# faketec-yuri_v1_1.net
KiCad netlist of a schematic drawn in Altium Designer
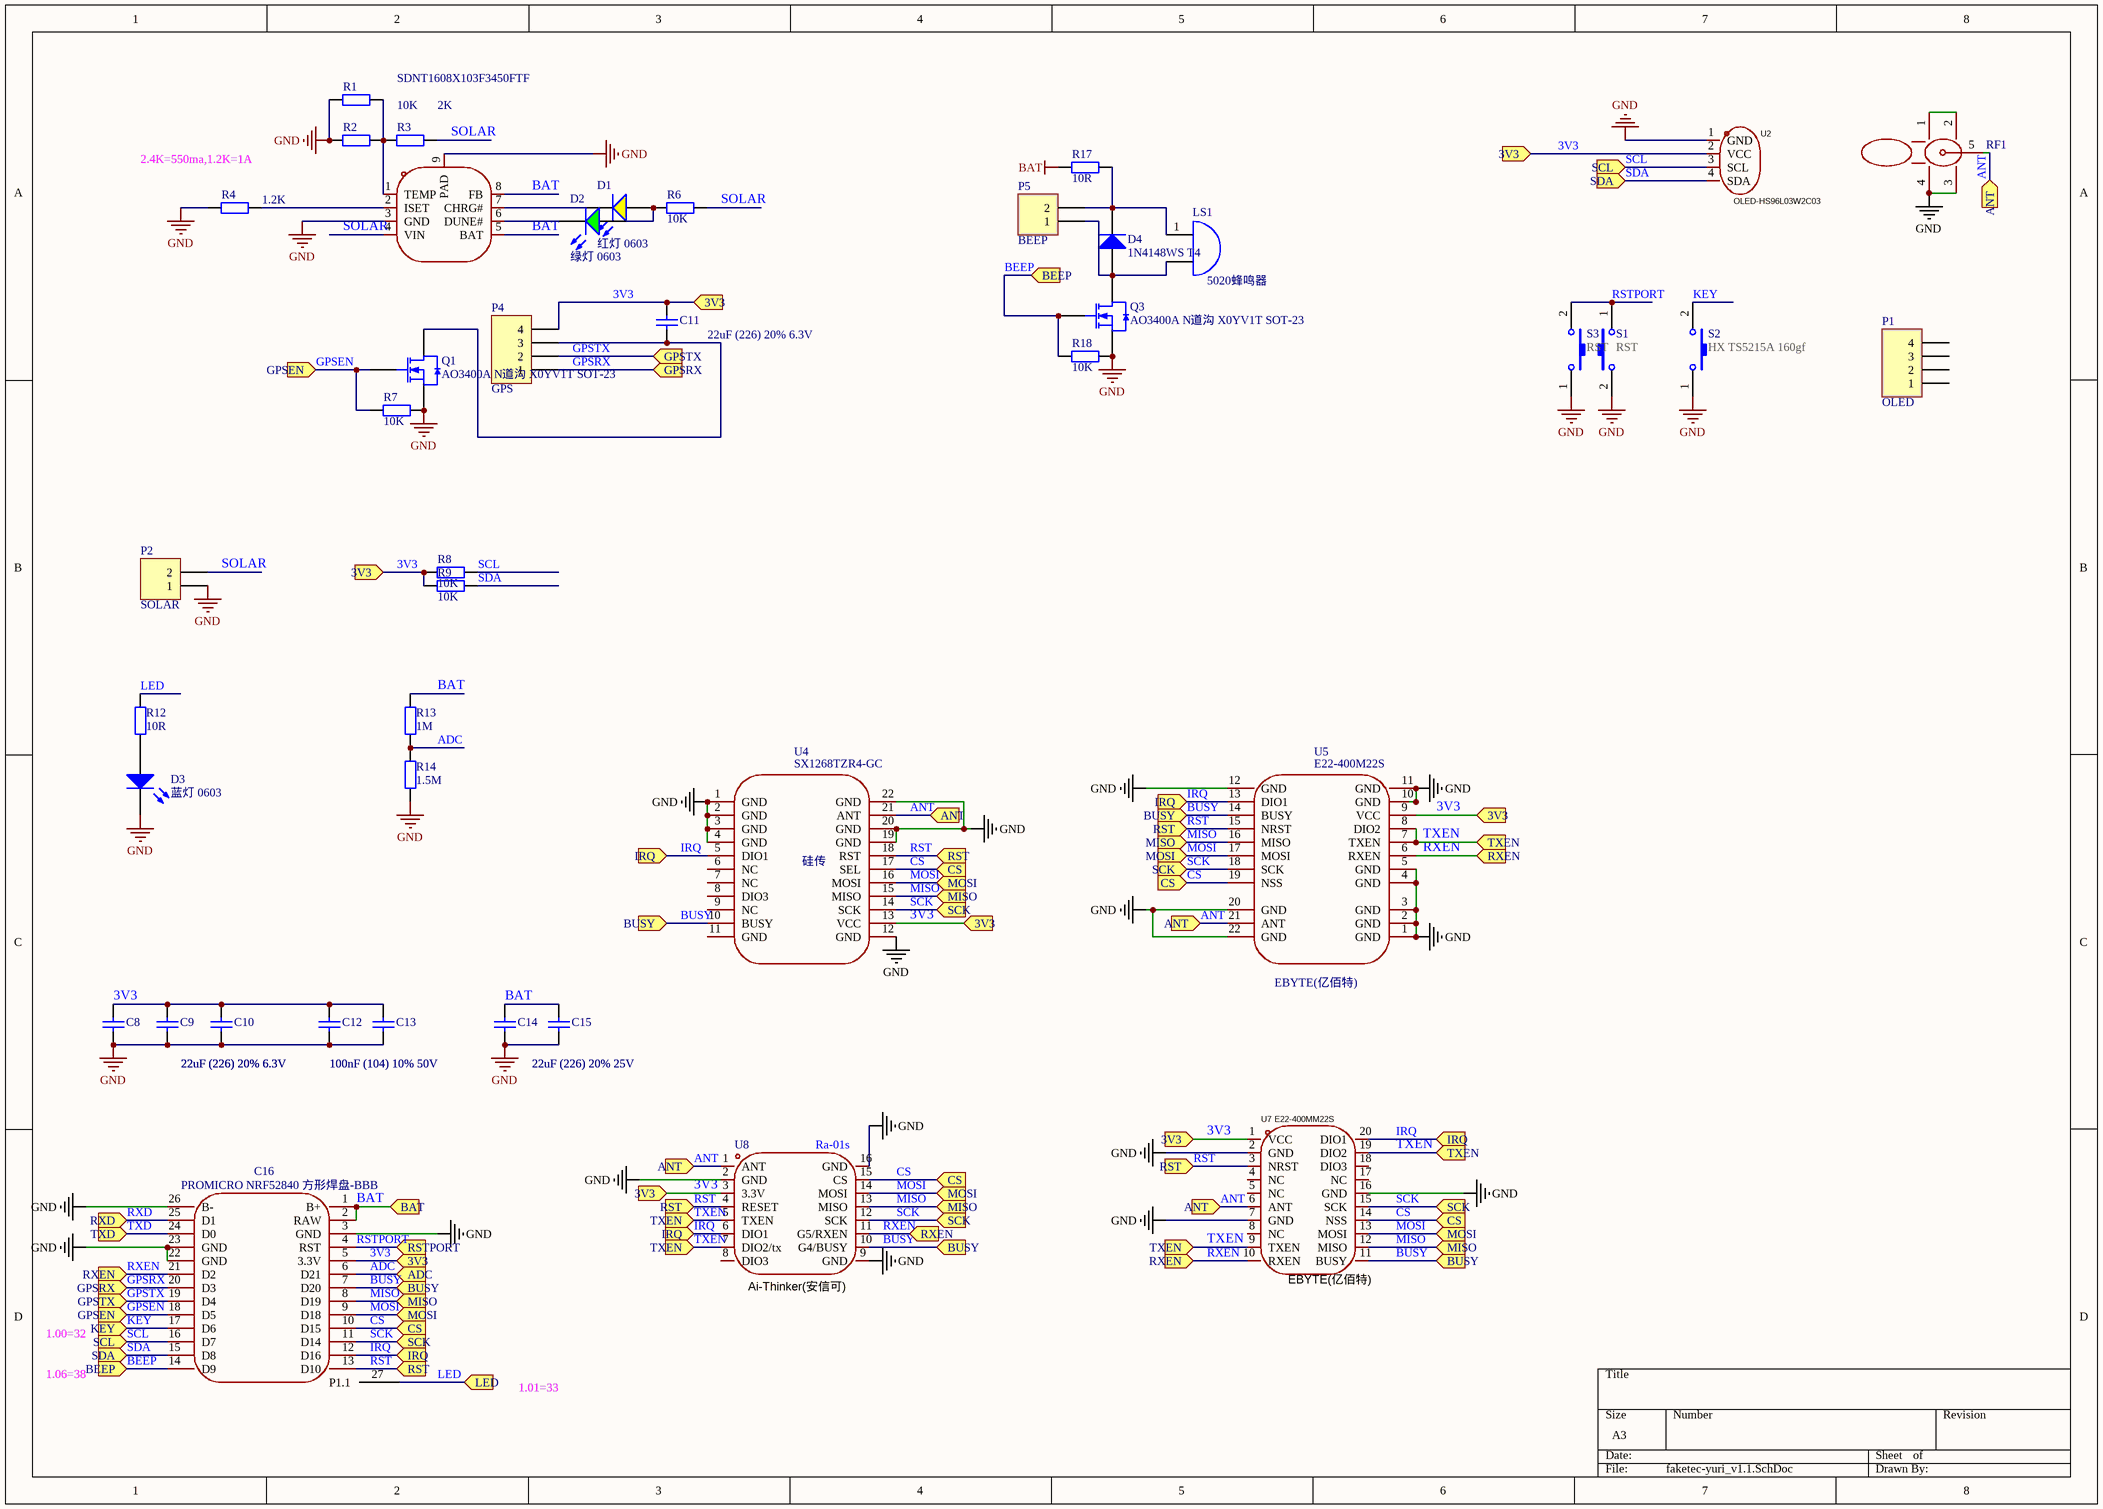
[diagram p0: faketec-yuri_v1.1.SchDoc]

(export (version "E")
  (design (tool "Eeschema 10.0.6"))
  (components
    (comp (ref "C8")
      (value "22uF (226) 20% 6.3V")
      (footprint "0603_C")
      (description "贴片电容")
      (libsource (lib "Miscellaneous Devices LC") (part "0603 22uF (226) 20% 6.3V"))
    )
    (comp (ref "C9")
      (value "22uF (226) 20% 6.3V")
      (footprint "0603_C")
      (description "贴片电容")
      (libsource (lib "Miscellaneous Devices LC") (part "0603 22uF (226) 20% 6.3V"))
    )
    (comp (ref "C10")
      (value "22uF (226) 20% 6.3V")
      (footprint "0603_C")
      (description "贴片电容")
      (libsource (lib "Miscellaneous Devices LC") (part "0603 22uF (226) 20% 6.3V"))
    )
    (comp (ref "C11")
      (value "22uF (226) 20% 6.3V")
      (footprint "0603_C")
      (description "贴片电容")
      (libsource (lib "Miscellaneous Devices LC") (part "0603 22uF (226) 20% 6.3V"))
    )
    (comp (ref "C12")
      (value "100nF (104) 10% 50V")
      (footprint "0603_C")
      (description "贴片电容")
      (libsource (lib "Cap") (part "0603 100nF (104) 10% 50V"))
    )
    (comp (ref "C13")
      (value "100nF (104) 10% 50V")
      (footprint "0603_C")
      (description "贴片电容")
      (libsource (lib "Cap") (part "0603 100nF (104) 10% 50V"))
    )
    (comp (ref "C14")
      (value "22uF (226) 20% 25V")
      (footprint "0805_C")
      (description "贴片电容")
      (libsource (lib "Cap") (part "0805 22uF (226) 20% 25V"))
    )
    (comp (ref "C15")
      (value "22uF (226) 20% 25V")
      (footprint "0805_C")
      (description "贴片电容")
      (libsource (lib "Cap") (part "0805 22uF (226) 20% 25V"))
    )
    (comp (ref "C16")
      (value "PROMICRO NRF52840 方形焊盘-BBB")
      (footprint "PROMICRO NRF52840")
      (libsource (lib "altium-import") (part "root_0_PROMICRO NRF52840 方形焊盘-BBB_"))
    )
    (comp (ref "D1")
      (value "红灯 0603")
      (footprint "0603_LED_S1")
      (description "发光二极管")
      (libsource (lib "LED") (part "0603 黄灯"))
    )
    (comp (ref "D2")
      (value "绿灯 0603")
      (footprint "0603_LED_S1")
      (description "发光二极管")
      (libsource (lib "LED") (part "0603 绿灯"))
    )
    (comp (ref "D3")
      (value "蓝灯 0603")
      (footprint "0603_LED_S1")
      (description "发光二极管")
      (libsource (lib "LED") (part "0603 蓝灯"))
    )
    (comp (ref "D4")
      (value "1N4148WS T4")
      (footprint "SOD-323")
      (description "二极管")
      (libsource (lib "Diode") (part "SOD-323 1N4148WS T4"))
    )
    (comp (ref "LS1")
      (value "5020蜂鸣器")
      (footprint "PB5020")
      (description "蜂鸣器")
      (libsource (lib "Miscellaneous Devices") (part "Bell"))
    )
    (comp (ref "P1")
      (value "OLED")
      (footprint "HT1.25-4")
      (description "Header, 4-Pin")
      (fields (field (name "PUBLISHER") "Altium Limited"))
      (libsource (lib "Miscellaneous Connectors") (part "Header 4"))
    )
    (comp (ref "P2")
      (value "SOLAR")
      (footprint "HDR1X2")
      (description "Header, 2-Pin")
      (fields (field (name "PUBLISHER") "Altium Limited"))
      (libsource (lib "Miscellaneous Connectors") (part "Header 2"))
    )
    (comp (ref "P4")
      (value "GPS")
      (footprint "HT1.25-4")
      (description "Header, 4-Pin")
      (fields (field (name "PUBLISHER") "Altium Limited"))
      (libsource (lib "Miscellaneous Connectors") (part "Header 4"))
    )
    (comp (ref "P5")
      (value "BEEP")
      (footprint "HDR1X2")
      (description "Header, 2-Pin")
      (fields (field (name "PUBLISHER") "Altium Limited"))
      (libsource (lib "Miscellaneous Connectors") (part "Header 2"))
    )
    (comp (ref "Q1")
      (value "AO3400A N道沟 X0YV1T SOT-23")
      (footprint "SOT-23-3L")
      (description "MOS(场效应管)")
      (libsource (lib "MOS") (part "AO3400A N道沟 X0YV1T SOT-23"))
    )
    (comp (ref "Q3")
      (value "AO3400A N道沟 X0YV1T SOT-23")
      (footprint "SOT-23-3L")
      (description "MOS(场效应管)")
      (libsource (lib "MOS") (part "AO3400A N道沟 X0YV1T SOT-23"))
    )
    (comp (ref "R1")
      (value "SDNT1608X103F3450FTF")
      (footprint "0603_R")
      (description "贴片电阻")
      (libsource (lib "RES") (part "0603 2.4KΩ (2401) 1%"))
    )
    (comp (ref "R2")
      (value "10K")
      (footprint "0603_R")
      (description "贴片电阻")
      (libsource (lib "RES") (part "0603 2.4KΩ (2401) 1%"))
    )
    (comp (ref "R3")
      (value "2K")
      (footprint "0603_R")
      (description "贴片电阻")
      (libsource (lib "RES") (part "0603 2.4KΩ (2401) 1%"))
    )
    (comp (ref "R4")
      (value "1.2K")
      (footprint "0603_R")
      (description "贴片电阻")
      (libsource (lib "RES") (part "0603 2.4KΩ (2401) 1%"))
    )
    (comp (ref "R6")
      (value "10K")
      (footprint "0603_R")
      (description "Resistor")
      (fields (field (name "PUBLISHER") "Altium Limited"))
      (libsource (lib "") (part "Res2_1"))
    )
    (comp (ref "R7")
      (value "10K")
      (footprint "0603_R")
      (description "贴片电阻")
      (libsource (lib "") (part "0603 2.4KΩ (2401) 1%_1"))
    )
    (comp (ref "R8")
      (value "10K")
      (footprint "0603_R")
      (description "Resistor")
      (fields (field (name "PUBLISHER") "Altium Limited"))
      (libsource (lib "") (part "Res2_1"))
    )
    (comp (ref "R9")
      (value "10K")
      (footprint "0603_R")
      (description "Resistor")
      (fields (field (name "PUBLISHER") "Altium Limited"))
      (libsource (lib "") (part "Res2_1"))
    )
    (comp (ref "R12")
      (value "10R")
      (footprint "0603_R")
      (description "贴片电阻")
      (libsource (lib "RES") (part "0603 10Ω (10R0) 1%"))
    )
    (comp (ref "R13")
      (value "1M")
      (footprint "0603_R")
      (description "Resistor")
      (fields (field (name "PUBLISHER") "Altium Limited"))
      (libsource (lib "Miscellaneous Devices") (part "Res2"))
    )
    (comp (ref "R14")
      (value "1.5M")
      (footprint "0603_R")
      (description "Resistor")
      (fields (field (name "PUBLISHER") "Altium Limited"))
      (libsource (lib "Miscellaneous Devices") (part "Res2"))
    )
    (comp (ref "R17")
      (value "10R")
      (footprint "0603_R")
      (description "贴片电容")
      (libsource (lib "Miscellaneous Devices LC") (part "0603 100KΩ (1003) 1%"))
    )
    (comp (ref "R18")
      (value "10K")
      (footprint "0603_R")
      (description "贴片电阻")
      (libsource (lib "") (part "0603 2.4KΩ (2401) 1%_1"))
    )
    (comp (ref "RF1")
      (value "SMA-KWE901")
      (footprint "SMA-TH_BWSMA-KWE-Z001")
      (fields (field (name "MANUFACTURER") "DreamLNK(骏晔科技)"))
      (libsource (lib "altium-import") (part "root_0_SMA-KWE901_"))
    )
    (comp (ref "S1")
      (value "RST")
      (footprint "BTIANLE-2x4x35")
      (description "3*6MM 轻触开关 贴片2脚 侧按 微动开关 按键开关 3*6*3.5卧式")
      (fields (field (name "PUBLISHER") "Altium Limited"))
      (libsource (lib "Miscellaneous Devices") (part "SW-PB"))
    )
    (comp (ref "S2")
      (value "HX TS5215A 160gf")
      (footprint "BTIANLE-35x7x35")
      (description "3*6MM 轻触开关 贴片2脚 侧按 微动开关 按键开关 3*6*3.5卧式")
      (fields (field (name "PUBLISHER") "Altium Limited"))
      (libsource (lib "Miscellaneous Devices") (part "SW-PB"))
    )
    (comp (ref "S3")
      (value "RST")
      (footprint "BTIANLE-2x4x35")
      (description "3*6MM 轻触开关 贴片2脚 侧按 微动开关 按键开关 3*6*3.5卧式")
      (fields (field (name "PUBLISHER") "Altium Limited"))
      (libsource (lib "Miscellaneous Devices") (part "SW-PB"))
    )
    (comp (ref "U2")
      (value "OLED-HS96L03W2C03")
      (footprint "OLED-TH_L27.8-W27.2-P2.54_C9900033791")
      (fields (field (name "MANUFACTURER") "HS(汉昇)") (field (name "MANUFACTURER PART") "HS96L03W2C03"))
      (libsource (lib "altium-import") (part "root_0_HS96L03W2C03_"))
    )
    (comp (ref "U3")
      (value "CN3163")
      (footprint "SOP-8_EP_150mil")
      (fields (field (name "MANUFACTURER") "CONSONANCE(上海如韵)"))
      (libsource (lib "altium-import") (part "root_0_CN3163_"))
    )
    (comp (ref "U4")
      (value "SX1268TZR4-GC")
      (footprint "SX1268TZR4-GC")
      (fields (field (name "MANUFACTURER") "硅传"))
      (libsource (lib "altium-import") (part "root_0_SX1268TZR4-GC_"))
    )
    (comp (ref "U5")
      (value "E22-400M22S")
      (footprint "E22-400M22S")
      (fields (field (name "MANUFACTURER") "EBYTE(亿佰特)"))
      (libsource (lib "altium-import") (part "root_0_E22-400M22S_"))
    )
    (comp (ref "U7")
      (value "E22-400MM22S")
      (footprint "E22-400MM22S")
      (fields (field (name "MANUFACTURER") "EBYTE(亿佰特)") (field (name "MANUFACTURER PART") "E220-400MM22S"))
      (libsource (lib "altium-import") (part "root_0_E22-400MM22S_"))
    )
    (comp (ref "U8")
      (value "Ra-01s")
      (footprint "RA-01")
      (description "SX1278LoRa扩频无线模块/超远10KM/433M/安信可Ra-01")
      (fields (field (name "MANUFACTURER") "Ai-Thinker(安信可)"))
      (libsource (lib "yuriSchlib1") (part "Ra-01"))
    )
  )
  (nets
    (net (code "1") (name "/3V3") (class "Default")
      (node (ref "C10") (pin "2") (pinfunction "2_2") (pintype "passive"))
      (node (ref "C11") (pin "2") (pinfunction "2_2") (pintype "passive"))
      (node (ref "C12") (pin "2") (pinfunction "2_2") (pintype "passive"))
      (node (ref "C13") (pin "2") (pinfunction "2_2") (pintype "passive"))
      (node (ref "C16") (pin "5") (pinfunction "3.3V_5") (pintype "passive"))
      (node (ref "C8") (pin "2") (pinfunction "2_2") (pintype "passive"))
      (node (ref "C9") (pin "2") (pinfunction "2_2") (pintype "passive"))
      (node (ref "P4") (pin "4") (pinfunction "4_4") (pintype "passive"))
      (node (ref "R8") (pin "2") (pinfunction "2_2") (pintype "passive"))
      (node (ref "R9") (pin "2") (pinfunction "2_2") (pintype "passive"))
      (node (ref "U2") (pin "2") (pinfunction "VCC_2") (pintype "passive"))
      (node (ref "U4") (pin "13") (pinfunction "VCC_13") (pintype "passive"))
      (node (ref "U5") (pin "9") (pinfunction "VCC_9") (pintype "passive"))
      (node (ref "U7") (pin "1") (pinfunction "VCC_1") (pintype "passive"))
      (node (ref "U8") (pin "3") (pinfunction "3.3V_3") (pintype "passive"))
    )
    (net (code "2") (name "/ADC") (class "Default")
      (node (ref "C16") (pin "6") (pinfunction "D21_6") (pintype "passive"))
      (node (ref "R13") (pin "1") (pinfunction "1_1") (pintype "passive"))
      (node (ref "R14") (pin "2") (pinfunction "2_2") (pintype "passive"))
    )
    (net (code "3") (name "/ANT") (class "Default")
      (node (ref "RF1") (pin "5") (pinfunction "5_5") (pintype "passive"))
      (node (ref "U4") (pin "21") (pinfunction "ANT_21") (pintype "passive"))
      (node (ref "U5") (pin "21") (pinfunction "ANT_21") (pintype "passive"))
      (node (ref "U7") (pin "6") (pinfunction "ANT_6") (pintype "passive"))
      (node (ref "U8") (pin "1") (pinfunction "ANT_1") (pintype "passive"))
    )
    (net (code "4") (name "/BEEP") (class "Default")
      (node (ref "C16") (pin "14") (pinfunction "D9_14") (pintype "passive"))
      (node (ref "Q3") (pin "1") (pinfunction "G_1") (pintype "passive"))
      (node (ref "R18") (pin "2") (pinfunction "2_2") (pintype "passive"))
    )
    (net (code "5") (name "/BUSY") (class "Default")
      (node (ref "C16") (pin "7") (pinfunction "D20_7") (pintype "passive"))
      (node (ref "U4") (pin "10") (pinfunction "BUSY_10") (pintype "passive"))
      (node (ref "U5") (pin "14") (pinfunction "BUSY_14") (pintype "passive"))
      (node (ref "U7") (pin "11") (pinfunction "BUSY_11") (pintype "passive"))
      (node (ref "U8") (pin "10") (pinfunction "G4/BUSY_10") (pintype "passive"))
    )
    (net (code "6") (name "/CS") (class "Default")
      (node (ref "C16") (pin "10") (pinfunction "D15_10") (pintype "passive"))
      (node (ref "U4") (pin "17") (pinfunction "SEL_17") (pintype "passive"))
      (node (ref "U5") (pin "19") (pinfunction "NSS_19") (pintype "passive"))
      (node (ref "U7") (pin "14") (pinfunction "NSS_14") (pintype "passive"))
      (node (ref "U8") (pin "15") (pinfunction "CS_15") (pintype "passive"))
    )
    (net (code "7") (name "/GPSEN") (class "Default")
      (node (ref "C16") (pin "18") (pinfunction "D5_18") (pintype "passive"))
      (node (ref "Q1") (pin "1") (pinfunction "G_1") (pintype "passive"))
      (node (ref "R7") (pin "2") (pinfunction "2_2") (pintype "passive"))
    )
    (net (code "8") (name "/GPSRX") (class "Default")
      (node (ref "C16") (pin "20") (pinfunction "D3_20") (pintype "passive"))
      (node (ref "P4") (pin "1") (pinfunction "1_1") (pintype "passive"))
    )
    (net (code "9") (name "/GPSTX") (class "Default")
      (node (ref "C16") (pin "19") (pinfunction "D4_19") (pintype "passive"))
      (node (ref "P4") (pin "2") (pinfunction "2_2") (pintype "passive"))
    )
    (net (code "10") (name "/IRQ") (class "Default")
      (node (ref "C16") (pin "12") (pinfunction "D16_12") (pintype "passive"))
      (node (ref "U4") (pin "5") (pinfunction "DIO1_5") (pintype "passive"))
      (node (ref "U5") (pin "13") (pinfunction "DIO1_13") (pintype "passive"))
      (node (ref "U7") (pin "20") (pinfunction "DIO1_20") (pintype "passive"))
      (node (ref "U8") (pin "6") (pinfunction "DIO1_6") (pintype "passive"))
    )
    (net (code "11") (name "/KEY") (class "Default")
      (node (ref "C16") (pin "17") (pinfunction "D6_17") (pintype "passive"))
      (node (ref "S2") (pin "2") (pinfunction "2_2") (pintype "passive"))
    )
    (net (code "12") (name "/LED") (class "Default")
      (node (ref "C16") (pin "27") (pinfunction "P1.1_27") (pintype "passive"))
      (node (ref "R12") (pin "1") (pinfunction "1_1") (pintype "passive"))
    )
    (net (code "13") (name "/MISO") (class "Default")
      (node (ref "C16") (pin "8") (pinfunction "D19_8") (pintype "passive"))
      (node (ref "U4") (pin "15") (pinfunction "MISO_15") (pintype "passive"))
      (node (ref "U5") (pin "16") (pinfunction "MISO_16") (pintype "passive"))
      (node (ref "U7") (pin "12") (pinfunction "MISO_12") (pintype "passive"))
      (node (ref "U8") (pin "13") (pinfunction "MISO_13") (pintype "passive"))
    )
    (net (code "14") (name "/MOSI") (class "Default")
      (node (ref "C16") (pin "9") (pinfunction "D18_9") (pintype "passive"))
      (node (ref "U4") (pin "16") (pinfunction "MOSI_16") (pintype "passive"))
      (node (ref "U5") (pin "17") (pinfunction "MOSI_17") (pintype "passive"))
      (node (ref "U7") (pin "13") (pinfunction "MOSI_13") (pintype "passive"))
      (node (ref "U8") (pin "14") (pinfunction "MOSI_14") (pintype "passive"))
    )
    (net (code "15") (name "/RST") (class "Default")
      (node (ref "C16") (pin "13") (pinfunction "D10_13") (pintype "passive"))
      (node (ref "U4") (pin "18") (pinfunction "RST_18") (pintype "passive"))
      (node (ref "U5") (pin "15") (pinfunction "NRST_15") (pintype "passive"))
      (node (ref "U7") (pin "3") (pinfunction "NRST_3") (pintype "passive"))
      (node (ref "U8") (pin "4") (pinfunction "RESET_4") (pintype "passive"))
    )
    (net (code "16") (name "/RSTPORT") (class "Default")
      (node (ref "C16") (pin "4") (pinfunction "RST_4") (pintype "passive"))
      (node (ref "S1") (pin "1") (pinfunction "1_1") (pintype "passive"))
      (node (ref "S3") (pin "2") (pinfunction "2_2") (pintype "passive"))
    )
    (net (code "17") (name "/RXD") (class "Default")
      (node (ref "C16") (pin "25") (pinfunction "D1_25") (pintype "passive"))
    )
    (net (code "18") (name "/RXEN") (class "Default")
      (node (ref "C16") (pin "21") (pinfunction "D2_21") (pintype "passive"))
      (node (ref "U5") (pin "6") (pinfunction "RXEN_6") (pintype "passive"))
      (node (ref "U7") (pin "10") (pinfunction "RXEN_10") (pintype "passive"))
      (node (ref "U8") (pin "11") (pinfunction "G5/RXEN_11") (pintype "passive"))
    )
    (net (code "19") (name "/SCK") (class "Default")
      (node (ref "C16") (pin "11") (pinfunction "D14_11") (pintype "passive"))
      (node (ref "U4") (pin "14") (pinfunction "SCK_14") (pintype "passive"))
      (node (ref "U5") (pin "18") (pinfunction "SCK_18") (pintype "passive"))
      (node (ref "U7") (pin "15") (pinfunction "SCK_15") (pintype "passive"))
      (node (ref "U8") (pin "12") (pinfunction "SCK_12") (pintype "passive"))
    )
    (net (code "20") (name "/SCL") (class "Default")
      (node (ref "C16") (pin "16") (pinfunction "D7_16") (pintype "passive"))
      (node (ref "R8") (pin "1") (pinfunction "1_1") (pintype "passive"))
      (node (ref "U2") (pin "3") (pinfunction "SCL_3") (pintype "passive"))
    )
    (net (code "21") (name "/SDA") (class "Default")
      (node (ref "C16") (pin "15") (pinfunction "D8_15") (pintype "passive"))
      (node (ref "R9") (pin "1") (pinfunction "1_1") (pintype "passive"))
      (node (ref "U2") (pin "4") (pinfunction "SDA_4") (pintype "passive"))
    )
    (net (code "22") (name "/SOLAR") (class "Default")
      (node (ref "P2") (pin "2") (pinfunction "2_2") (pintype "passive"))
      (node (ref "R3") (pin "2") (pinfunction "2_2") (pintype "passive"))
      (node (ref "R6") (pin "1") (pinfunction "1_1") (pintype "passive"))
      (node (ref "U3") (pin "4") (pinfunction "VIN_4") (pintype "passive"))
    )
    (net (code "23") (name "/TXD") (class "Default")
      (node (ref "C16") (pin "24") (pinfunction "D0_24") (pintype "passive"))
    )
    (net (code "24") (name "/TXEN") (class "Default")
      (node (ref "U5") (pin "7") (pinfunction "TXEN_7") (pintype "passive"))
      (node (ref "U5") (pin "8") (pinfunction "DIO2_8") (pintype "passive"))
      (node (ref "U7") (pin "19") (pinfunction "DIO2_19") (pintype "passive"))
      (node (ref "U7") (pin "9") (pinfunction "TXEN_9") (pintype "passive"))
      (node (ref "U8") (pin "5") (pinfunction "TXEN_5") (pintype "passive"))
      (node (ref "U8") (pin "7") (pinfunction "DIO2/tx_7") (pintype "passive"))
    )
    (net (code "25") (name "BAT") (class "Default")
      (node (ref "C14") (pin "2") (pinfunction "2_2") (pintype "passive"))
      (node (ref "C15") (pin "2") (pinfunction "2_2") (pintype "passive"))
      (node (ref "C16") (pin "1") (pinfunction "B+_1") (pintype "passive"))
      (node (ref "C16") (pin "2") (pinfunction "RAW_2") (pintype "passive"))
      (node (ref "R13") (pin "2") (pinfunction "2_2") (pintype "passive"))
      (node (ref "R17") (pin "2") (pinfunction "2_2") (pintype "passive"))
      (node (ref "U3") (pin "5") (pinfunction "BAT_5") (pintype "passive"))
      (node (ref "U3") (pin "8") (pinfunction "FB_8") (pintype "passive"))
    )
    (net (code "26") (name "GND") (class "Default")
      (node (ref "C10") (pin "1") (pinfunction "1_1") (pintype "passive"))
      (node (ref "C12") (pin "1") (pinfunction "1_1") (pintype "passive"))
      (node (ref "C13") (pin "1") (pinfunction "1_1") (pintype "passive"))
      (node (ref "C14") (pin "1") (pinfunction "1_1") (pintype "passive"))
      (node (ref "C15") (pin "1") (pinfunction "1_1") (pintype "passive"))
      (node (ref "C16") (pin "22") (pinfunction "GND_22") (pintype "passive"))
      (node (ref "C16") (pin "23") (pinfunction "GND_23") (pintype "passive"))
      (node (ref "C16") (pin "26") (pinfunction "B-_26") (pintype "passive"))
      (node (ref "C16") (pin "3") (pinfunction "GND_3") (pintype "passive"))
      (node (ref "C8") (pin "1") (pinfunction "1_1") (pintype "passive"))
      (node (ref "C9") (pin "1") (pinfunction "1_1") (pintype "passive"))
      (node (ref "D3") (pin "K") (pinfunction "K_K") (pintype "passive"))
      (node (ref "P2") (pin "1") (pinfunction "1_1") (pintype "passive"))
      (node (ref "Q1") (pin "2") (pinfunction "S_2") (pintype "passive"))
      (node (ref "Q3") (pin "2") (pinfunction "S_2") (pintype "passive"))
      (node (ref "R1") (pin "1") (pinfunction "1_1") (pintype "passive"))
      (node (ref "R14") (pin "1") (pinfunction "1_1") (pintype "passive"))
      (node (ref "R18") (pin "1") (pinfunction "1_1") (pintype "passive"))
      (node (ref "R2") (pin "1") (pinfunction "1_1") (pintype "passive"))
      (node (ref "R4") (pin "1") (pinfunction "1_1") (pintype "passive"))
      (node (ref "R7") (pin "1") (pinfunction "1_1") (pintype "passive"))
      (node (ref "RF1") (pin "3") (pinfunction "3_3") (pintype "passive"))
      (node (ref "RF1") (pin "4") (pinfunction "4_4") (pintype "passive"))
      (node (ref "S1") (pin "2") (pinfunction "2_2") (pintype "passive"))
      (node (ref "S2") (pin "1") (pinfunction "1_1") (pintype "passive"))
      (node (ref "S3") (pin "1") (pinfunction "1_1") (pintype "passive"))
      (node (ref "U2") (pin "1") (pinfunction "GND_1") (pintype "passive"))
      (node (ref "U3") (pin "3") (pinfunction "GND_3") (pintype "passive"))
      (node (ref "U3") (pin "9") (pinfunction "PAD_9") (pintype "passive"))
      (node (ref "U4") (pin "1") (pinfunction "GND_1") (pintype "passive"))
      (node (ref "U4") (pin "12") (pinfunction "GND_12") (pintype "passive"))
      (node (ref "U4") (pin "19") (pinfunction "GND_19") (pintype "passive"))
      (node (ref "U4") (pin "2") (pinfunction "GND_2") (pintype "passive"))
      (node (ref "U4") (pin "20") (pinfunction "GND_20") (pintype "passive"))
      (node (ref "U4") (pin "22") (pinfunction "GND_22") (pintype "passive"))
      (node (ref "U4") (pin "3") (pinfunction "GND_3") (pintype "passive"))
      (node (ref "U4") (pin "4") (pinfunction "GND_4") (pintype "passive"))
      (node (ref "U5") (pin "1") (pinfunction "GND_1") (pintype "passive"))
      (node (ref "U5") (pin "10") (pinfunction "GND_10") (pintype "passive"))
      (node (ref "U5") (pin "11") (pinfunction "GND_11") (pintype "passive"))
      (node (ref "U5") (pin "12") (pinfunction "GND_12") (pintype "passive"))
      (node (ref "U5") (pin "2") (pinfunction "GND_2") (pintype "passive"))
      (node (ref "U5") (pin "20") (pinfunction "GND_20") (pintype "passive"))
      (node (ref "U5") (pin "22") (pinfunction "GND_22") (pintype "passive"))
      (node (ref "U5") (pin "3") (pinfunction "GND_3") (pintype "passive"))
      (node (ref "U5") (pin "4") (pinfunction "GND_4") (pintype "passive"))
      (node (ref "U5") (pin "5") (pinfunction "GND_5") (pintype "passive"))
      (node (ref "U7") (pin "16") (pinfunction "GND_16") (pintype "passive"))
      (node (ref "U7") (pin "2") (pinfunction "GND_2") (pintype "passive"))
      (node (ref "U7") (pin "7") (pinfunction "GND_7") (pintype "passive"))
      (node (ref "U8") (pin "16") (pinfunction "GND_16") (pintype "passive"))
      (node (ref "U8") (pin "2") (pinfunction "GND_2") (pintype "passive"))
      (node (ref "U8") (pin "9") (pinfunction "GND_9") (pintype "passive"))
    )
    (net (code "27") (name "Net-(D1-PadA)") (class "Default")
      (node (ref "D1") (pin "A") (pinfunction "A_A") (pintype "passive"))
      (node (ref "D2") (pin "A") (pinfunction "A_A") (pintype "passive"))
      (node (ref "R6") (pin "2") (pinfunction "2_2") (pintype "passive"))
    )
    (net (code "28") (name "Net-(D3-PadA)") (class "Default")
      (node (ref "D3") (pin "A") (pinfunction "A_A") (pintype "passive"))
      (node (ref "R12") (pin "2") (pinfunction "2_2") (pintype "passive"))
    )
    (net (code "29") (name "Net-(D4-A)") (class "Default")
      (node (ref "D4") (pin "1") (pinfunction "A_1") (pintype "passive"))
      (node (ref "LS1") (pin "2") (pinfunction "B_2") (pintype "passive"))
      (node (ref "P5") (pin "1") (pinfunction "1_1") (pintype "passive"))
      (node (ref "Q3") (pin "3") (pinfunction "D_3") (pintype "passive"))
    )
    (net (code "30") (name "Net-(D4-K)") (class "Default")
      (node (ref "D4") (pin "2") (pinfunction "K_2") (pintype "passive"))
      (node (ref "LS1") (pin "1") (pinfunction "A_1") (pintype "passive"))
      (node (ref "P5") (pin "2") (pinfunction "2_2") (pintype "passive"))
      (node (ref "R17") (pin "1") (pinfunction "1_1") (pintype "passive"))
    )
    (net (code "31") (name "Net-(Q1-D)") (class "Default")
      (node (ref "C11") (pin "1") (pinfunction "1_1") (pintype "passive"))
      (node (ref "P4") (pin "3") (pinfunction "3_3") (pintype "passive"))
      (node (ref "Q1") (pin "3") (pinfunction "D_3") (pintype "passive"))
    )
    (net (code "32") (name "Net-(RF1-Pad1)") (class "Default")
      (node (ref "RF1") (pin "1") (pinfunction "1_1") (pintype "passive"))
      (node (ref "RF1") (pin "2") (pinfunction "2_2") (pintype "passive"))
    )
    (net (code "33") (name "Net-(U3-CHRG#)") (class "Default")
      (node (ref "D1") (pin "K") (pinfunction "K_K") (pintype "passive"))
      (node (ref "U3") (pin "7") (pinfunction "CHRG#_7") (pintype "passive"))
    )
    (net (code "34") (name "Net-(U3-DUNE#)") (class "Default")
      (node (ref "D2") (pin "K") (pinfunction "K_K") (pintype "passive"))
      (node (ref "U3") (pin "6") (pinfunction "DUNE#_6") (pintype "passive"))
    )
    (net (code "35") (name "Net-(U3-ISET)") (class "Default")
      (node (ref "R4") (pin "2") (pinfunction "2_2") (pintype "passive"))
      (node (ref "U3") (pin "2") (pinfunction "ISET_2") (pintype "passive"))
    )
    (net (code "36") (name "Net-(U3-TEMP)") (class "Default")
      (node (ref "R1") (pin "2") (pinfunction "2_2") (pintype "passive"))
      (node (ref "R2") (pin "2") (pinfunction "2_2") (pintype "passive"))
      (node (ref "R3") (pin "1") (pinfunction "1_1") (pintype "passive"))
      (node (ref "U3") (pin "1") (pinfunction "TEMP_1") (pintype "passive"))
    )
    (net (code "37") (name "unconnected-(P1-Pad1)") (class "Default")
      (node (ref "P1") (pin "1") (pinfunction "1_1") (pintype "passive"))
    )
    (net (code "38") (name "unconnected-(P1-Pad2)") (class "Default")
      (node (ref "P1") (pin "2") (pinfunction "2_2") (pintype "passive"))
    )
    (net (code "39") (name "unconnected-(P1-Pad3)") (class "Default")
      (node (ref "P1") (pin "3") (pinfunction "3_3") (pintype "passive"))
    )
    (net (code "40") (name "unconnected-(P1-Pad4)") (class "Default")
      (node (ref "P1") (pin "4") (pinfunction "4_4") (pintype "passive"))
    )
    (net (code "41") (name "unconnected-(U4-DIO3-Pad8)") (class "Default")
      (node (ref "U4") (pin "8") (pinfunction "DIO3_8") (pintype "passive"))
    )
    (net (code "42") (name "unconnected-(U4-GND-Pad11)") (class "Default")
      (node (ref "U4") (pin "11") (pinfunction "GND_11") (pintype "passive"))
    )
    (net (code "43") (name "unconnected-(U4-NC-Pad6)") (class "Default")
      (node (ref "U4") (pin "6") (pinfunction "NC_6") (pintype "passive"))
    )
    (net (code "44") (name "unconnected-(U4-NC-Pad7)") (class "Default")
      (node (ref "U4") (pin "7") (pinfunction "NC_7") (pintype "passive"))
    )
    (net (code "45") (name "unconnected-(U4-NC-Pad9)") (class "Default")
      (node (ref "U4") (pin "9") (pinfunction "NC_9") (pintype "passive"))
    )
    (net (code "46") (name "unconnected-(U7-DIO3-Pad18)") (class "Default")
      (node (ref "U7") (pin "18") (pinfunction "DIO3_18") (pintype "passive"))
    )
    (net (code "47") (name "unconnected-(U7-NC-Pad4)") (class "Default")
      (node (ref "U7") (pin "4") (pinfunction "NC_4") (pintype "passive"))
    )
    (net (code "48") (name "unconnected-(U7-NC-Pad5)") (class "Default")
      (node (ref "U7") (pin "5") (pinfunction "NC_5") (pintype "passive"))
    )
    (net (code "49") (name "unconnected-(U7-NC-Pad8)") (class "Default")
      (node (ref "U7") (pin "8") (pinfunction "NC_8") (pintype "passive"))
    )
    (net (code "50") (name "unconnected-(U7-NC-Pad17)") (class "Default")
      (node (ref "U7") (pin "17") (pinfunction "NC_17") (pintype "passive"))
    )
    (net (code "51") (name "unconnected-(U8-DIO3-Pad8)") (class "Default")
      (node (ref "U8") (pin "8") (pinfunction "DIO3_8") (pintype "passive"))
    )
  )
)
